# radio1.net
KiCad netlist of a schematic drawn in EAGLE
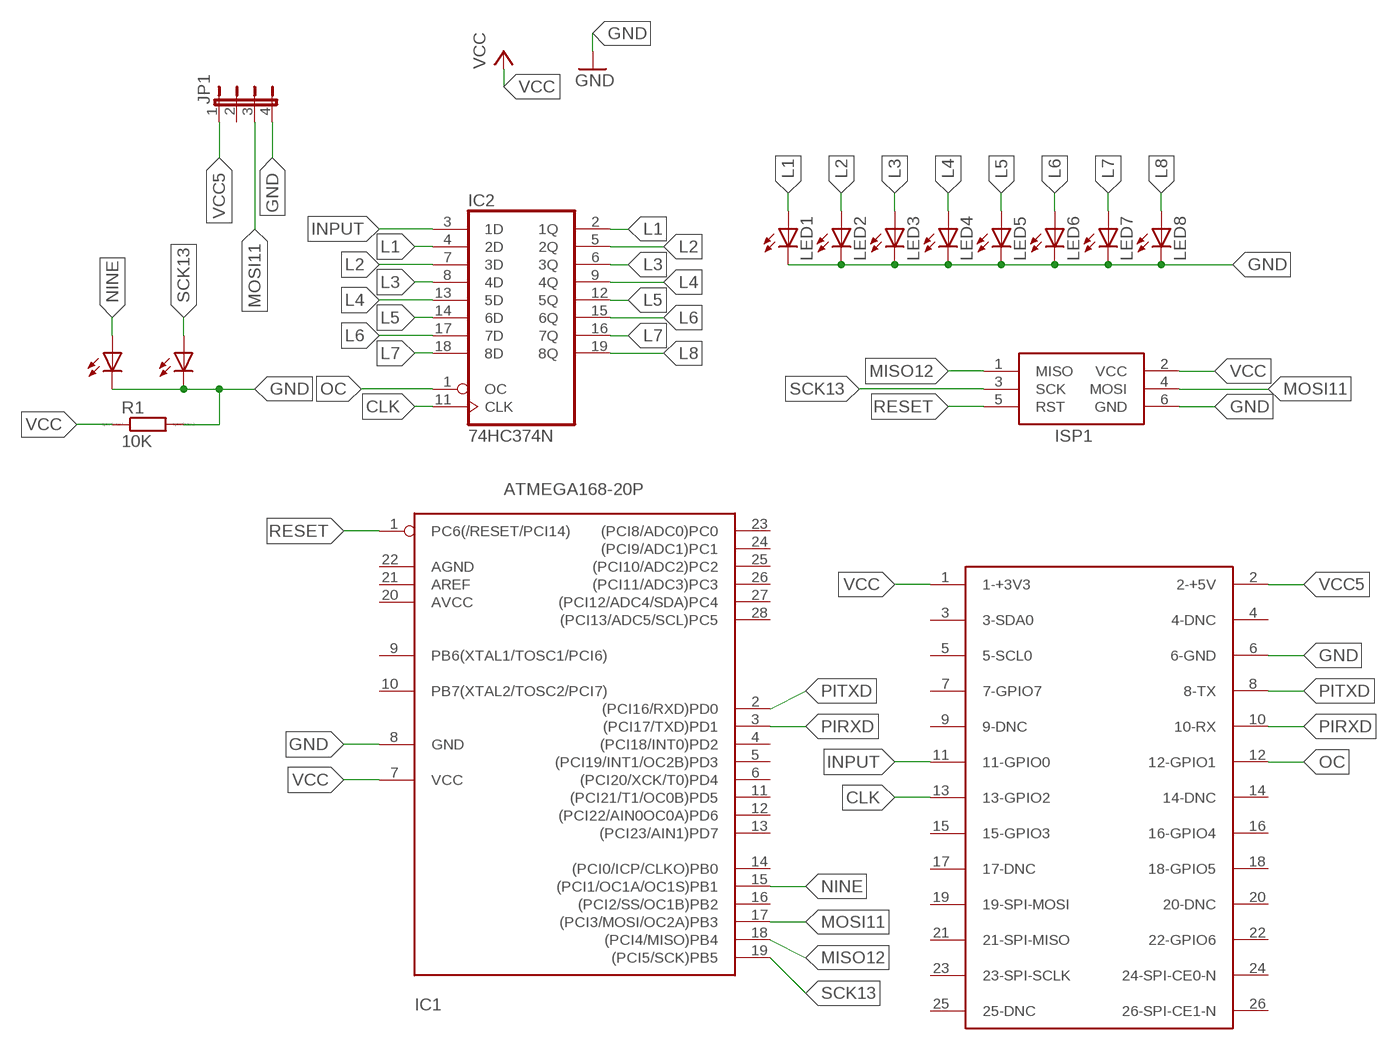
[diagram p0: schematic, sheet 1]

(export (version "E")
  (design (tool "Eeschema 10.0.6"))
  (components
    (comp (ref "IC1")
      (value "ATMEGA168-20P")
      (footprint "eagle-import:DIL28-3")
      (libsource (lib "eagle-import") (part "ATMEGA168P-20"))
    )
    (comp (ref "IC2")
      (value "74HC374N")
      (footprint "eagle-import:DIL20")
      (libsource (lib "eagle-import") (part "74374NHC"))
    )
    (comp (ref "ISP1")
      (value "AVRISP-6")
      (footprint "eagle-import:AVRISP")
      (libsource (lib "eagle-import") (part "AVRISP-6"))
    )
    (comp (ref "JP1")
      (value "JP4E")
      (footprint "eagle-import:JP4")
      (libsource (lib "eagle-import") (part "JP4E"))
    )
    (comp (ref "LED1")
      (value "LED3MM")
      (footprint "eagle-import:LED3MM")
      (libsource (lib "eagle-import") (part "LED3MM"))
    )
    (comp (ref "LED2")
      (value "LED3MM")
      (footprint "eagle-import:LED3MM")
      (libsource (lib "eagle-import") (part "LED3MM"))
    )
    (comp (ref "LED3")
      (value "LED3MM")
      (footprint "eagle-import:LED3MM")
      (libsource (lib "eagle-import") (part "LED3MM"))
    )
    (comp (ref "LED4")
      (value "LED3MM")
      (footprint "eagle-import:LED3MM")
      (libsource (lib "eagle-import") (part "LED3MM"))
    )
    (comp (ref "LED5")
      (value "LED3MM")
      (footprint "eagle-import:LED3MM")
      (libsource (lib "eagle-import") (part "LED3MM"))
    )
    (comp (ref "LED6")
      (value "LED3MM")
      (footprint "eagle-import:LED3MM")
      (libsource (lib "eagle-import") (part "LED3MM"))
    )
    (comp (ref "LED7")
      (value "LED3MM")
      (footprint "eagle-import:LED3MM")
      (libsource (lib "eagle-import") (part "LED3MM"))
    )
    (comp (ref "LED8")
      (value "LED3MM")
      (footprint "eagle-import:LED3MM")
      (libsource (lib "eagle-import") (part "LED3MM"))
    )
    (comp (ref "LED9")
      (value "LED3MM")
      (footprint "eagle-import:LED3MM")
      (libsource (lib "eagle-import") (part "LED3MM"))
    )
    (comp (ref "LED10")
      (value "LED3MM")
      (footprint "eagle-import:LED3MM")
      (libsource (lib "eagle-import") (part "LED3MM"))
    )
    (comp (ref "R1")
      (value "10K")
      (footprint "eagle-import:0204_7")
      (libsource (lib "eagle-import") (part "R-EU_0204_7"))
    )
    (comp (ref "U$1")
      (value "RASPBERRY-PI")
      (footprint "eagle-import:RASPBERRY-PI")
      (libsource (lib "eagle-import") (part "RASPBERRY-PI"))
    )
  )
  (nets
    (net (code "1") (name "CLK") (class "Default")
      (node (ref "IC2") (pin "11") (pinfunction "CLK_11") (pintype "input"))
      (node (ref "U$1") (pin "13") (pinfunction "13-GPIO2_13") (pintype "bidirectional"))
    )
    (net (code "2") (name "GND") (class "Default")
      (node (ref "IC1") (pin "8") (pinfunction "GND_8") (pintype "bidirectional"))
      (node (ref "ISP1") (pin "6") (pinfunction "GND_6") (pintype "power_in"))
      (node (ref "JP1") (pin "4") (pinfunction "4_4") (pintype "passive"))
      (node (ref "LED1") (pin "K") (pinfunction "C_K") (pintype "passive"))
      (node (ref "LED10") (pin "K") (pinfunction "C_K") (pintype "passive"))
      (node (ref "LED2") (pin "K") (pinfunction "C_K") (pintype "passive"))
      (node (ref "LED3") (pin "K") (pinfunction "C_K") (pintype "passive"))
      (node (ref "LED4") (pin "K") (pinfunction "C_K") (pintype "passive"))
      (node (ref "LED5") (pin "K") (pinfunction "C_K") (pintype "passive"))
      (node (ref "LED6") (pin "K") (pinfunction "C_K") (pintype "passive"))
      (node (ref "LED7") (pin "K") (pinfunction "C_K") (pintype "passive"))
      (node (ref "LED8") (pin "K") (pinfunction "C_K") (pintype "passive"))
      (node (ref "LED9") (pin "K") (pinfunction "C_K") (pintype "passive"))
      (node (ref "R1") (pin "2") (pinfunction "2_2") (pintype "passive"))
      (node (ref "U$1") (pin "6") (pinfunction "6-GND_6") (pintype "bidirectional"))
    )
    (net (code "3") (name "INPUT") (class "Default")
      (node (ref "IC2") (pin "3") (pinfunction "1D_3") (pintype "input"))
      (node (ref "U$1") (pin "11") (pinfunction "11-GPIO0_11") (pintype "bidirectional"))
    )
    (net (code "4") (name "L1") (class "Default")
      (node (ref "IC2") (pin "2") (pinfunction "1Q_2") (pintype "tri_state"))
      (node (ref "IC2") (pin "4") (pinfunction "2D_4") (pintype "input"))
      (node (ref "LED1") (pin "A") (pinfunction "A_A") (pintype "passive"))
    )
    (net (code "5") (name "L2") (class "Default")
      (node (ref "IC2") (pin "5") (pinfunction "2Q_5") (pintype "tri_state"))
      (node (ref "IC2") (pin "7") (pinfunction "3D_7") (pintype "input"))
      (node (ref "LED2") (pin "A") (pinfunction "A_A") (pintype "passive"))
    )
    (net (code "6") (name "L3") (class "Default")
      (node (ref "IC2") (pin "6") (pinfunction "3Q_6") (pintype "tri_state"))
      (node (ref "IC2") (pin "8") (pinfunction "4D_8") (pintype "input"))
      (node (ref "LED3") (pin "A") (pinfunction "A_A") (pintype "passive"))
    )
    (net (code "7") (name "L4") (class "Default")
      (node (ref "IC2") (pin "13") (pinfunction "5D_13") (pintype "input"))
      (node (ref "IC2") (pin "9") (pinfunction "4Q_9") (pintype "tri_state"))
      (node (ref "LED4") (pin "A") (pinfunction "A_A") (pintype "passive"))
    )
    (net (code "8") (name "L5") (class "Default")
      (node (ref "IC2") (pin "12") (pinfunction "5Q_12") (pintype "tri_state"))
      (node (ref "IC2") (pin "14") (pinfunction "6D_14") (pintype "input"))
      (node (ref "LED5") (pin "A") (pinfunction "A_A") (pintype "passive"))
    )
    (net (code "9") (name "L6") (class "Default")
      (node (ref "IC2") (pin "15") (pinfunction "6Q_15") (pintype "tri_state"))
      (node (ref "IC2") (pin "17") (pinfunction "7D_17") (pintype "input"))
      (node (ref "LED6") (pin "A") (pinfunction "A_A") (pintype "passive"))
    )
    (net (code "10") (name "L7") (class "Default")
      (node (ref "IC2") (pin "16") (pinfunction "7Q_16") (pintype "tri_state"))
      (node (ref "IC2") (pin "18") (pinfunction "8D_18") (pintype "input"))
      (node (ref "LED7") (pin "A") (pinfunction "A_A") (pintype "passive"))
    )
    (net (code "11") (name "L8") (class "Default")
      (node (ref "IC2") (pin "19") (pinfunction "8Q_19") (pintype "tri_state"))
      (node (ref "LED8") (pin "A") (pinfunction "A_A") (pintype "passive"))
    )
    (net (code "12") (name "MISO12") (class "Default")
      (node (ref "IC1") (pin "18") (pinfunction "(PCI4/MISO)PB4_18") (pintype "bidirectional"))
      (node (ref "ISP1") (pin "1") (pinfunction "MISO_1") (pintype "input"))
    )
    (net (code "13") (name "MOSI11") (class "Default")
      (node (ref "IC1") (pin "17") (pinfunction "(PCI3/MOSI/OC2A)PB3_17") (pintype "bidirectional"))
      (node (ref "ISP1") (pin "4") (pinfunction "MOSI_4") (pintype "output"))
      (node (ref "JP1") (pin "3") (pinfunction "3_3") (pintype "passive"))
    )
    (net (code "14") (name "NINE") (class "Default")
      (node (ref "IC1") (pin "15") (pinfunction "(PCI1/OC1A/OC1S)PB1_15") (pintype "bidirectional"))
      (node (ref "LED9") (pin "A") (pinfunction "A_A") (pintype "passive"))
    )
    (net (code "15") (name "OC") (class "Default")
      (node (ref "IC2") (pin "1") (pinfunction "OC_1") (pintype "input"))
      (node (ref "U$1") (pin "12") (pinfunction "12-GPIO1_12") (pintype "bidirectional"))
    )
    (net (code "16") (name "PIRXD") (class "Default")
      (node (ref "IC1") (pin "3") (pinfunction "(PCI17/TXD)PD1_3") (pintype "bidirectional"))
      (node (ref "U$1") (pin "10") (pinfunction "10-RX_10") (pintype "bidirectional"))
    )
    (net (code "17") (name "PITXD") (class "Default")
      (node (ref "IC1") (pin "2") (pinfunction "(PCI16/RXD)PD0_2") (pintype "bidirectional"))
      (node (ref "U$1") (pin "8") (pinfunction "8-TX_8") (pintype "bidirectional"))
    )
    (net (code "18") (name "RESET") (class "Default")
      (node (ref "IC1") (pin "1") (pinfunction "PC6(/RESET/PCI14)_1") (pintype "bidirectional"))
      (node (ref "ISP1") (pin "5") (pinfunction "RST_5") (pintype "output"))
    )
    (net (code "19") (name "SCK13") (class "Default")
      (node (ref "IC1") (pin "19") (pinfunction "(PCI5/SCK)PB5_19") (pintype "bidirectional"))
      (node (ref "ISP1") (pin "3") (pinfunction "SCK_3") (pintype "output"))
      (node (ref "LED10") (pin "A") (pinfunction "A_A") (pintype "passive"))
    )
    (net (code "20") (name "VCC") (class "Default")
      (node (ref "IC1") (pin "7") (pinfunction "VCC_7") (pintype "bidirectional"))
      (node (ref "ISP1") (pin "2") (pinfunction "VCC_2") (pintype "power_in"))
      (node (ref "R1") (pin "1") (pinfunction "1_1") (pintype "passive"))
      (node (ref "U$1") (pin "1") (pinfunction "1-+3V3_1") (pintype "bidirectional"))
    )
    (net (code "21") (name "VCC5") (class "Default")
      (node (ref "JP1") (pin "1") (pinfunction "1_1") (pintype "passive"))
      (node (ref "U$1") (pin "2") (pinfunction "2-+5V_2") (pintype "bidirectional"))
    )
    (net (code "22") (name "unconnected-(IC1-(PCI0{slash}ICP{slash}CLKO)PB0-Pad14)") (class "Default")
      (node (ref "IC1") (pin "14") (pinfunction "(PCI0/ICP/CLKO)PB0_14") (pintype "bidirectional"))
    )
    (net (code "23") (name "unconnected-(IC1-(PCI2{slash}SS{slash}OC1B)PB2-Pad16)") (class "Default")
      (node (ref "IC1") (pin "16") (pinfunction "(PCI2/SS/OC1B)PB2_16") (pintype "bidirectional"))
    )
    (net (code "24") (name "unconnected-(IC1-(PCI8{slash}ADC0)PC0-Pad23)") (class "Default")
      (node (ref "IC1") (pin "23") (pinfunction "(PCI8/ADC0)PC0_23") (pintype "bidirectional"))
    )
    (net (code "25") (name "unconnected-(IC1-(PCI9{slash}ADC1)PC1-Pad24)") (class "Default")
      (node (ref "IC1") (pin "24") (pinfunction "(PCI9/ADC1)PC1_24") (pintype "bidirectional"))
    )
    (net (code "26") (name "unconnected-(IC1-(PCI10{slash}ADC2)PC2-Pad25)") (class "Default")
      (node (ref "IC1") (pin "25") (pinfunction "(PCI10/ADC2)PC2_25") (pintype "bidirectional"))
    )
    (net (code "27") (name "unconnected-(IC1-(PCI11{slash}ADC3)PC3-Pad26)") (class "Default")
      (node (ref "IC1") (pin "26") (pinfunction "(PCI11/ADC3)PC3_26") (pintype "bidirectional"))
    )
    (net (code "28") (name "unconnected-(IC1-(PCI12{slash}ADC4{slash}SDA)PC4-Pad27)") (class "Default")
      (node (ref "IC1") (pin "27") (pinfunction "(PCI12/ADC4/SDA)PC4_27") (pintype "bidirectional"))
    )
    (net (code "29") (name "unconnected-(IC1-(PCI13{slash}ADC5{slash}SCL)PC5-Pad28)") (class "Default")
      (node (ref "IC1") (pin "28") (pinfunction "(PCI13/ADC5/SCL)PC5_28") (pintype "bidirectional"))
    )
    (net (code "30") (name "unconnected-(IC1-(PCI18{slash}INT0)PD2-Pad4)") (class "Default")
      (node (ref "IC1") (pin "4") (pinfunction "(PCI18/INT0)PD2_4") (pintype "bidirectional"))
    )
    (net (code "31") (name "unconnected-(IC1-(PCI19{slash}INT1{slash}OC2B)PD3-Pad5)") (class "Default")
      (node (ref "IC1") (pin "5") (pinfunction "(PCI19/INT1/OC2B)PD3_5") (pintype "bidirectional"))
    )
    (net (code "32") (name "unconnected-(IC1-(PCI20{slash}XCK{slash}T0)PD4-Pad6)") (class "Default")
      (node (ref "IC1") (pin "6") (pinfunction "(PCI20/XCK/T0)PD4_6") (pintype "bidirectional"))
    )
    (net (code "33") (name "unconnected-(IC1-(PCI21{slash}T1{slash}OC0B)PD5-Pad11)") (class "Default")
      (node (ref "IC1") (pin "11") (pinfunction "(PCI21/T1/OC0B)PD5_11") (pintype "bidirectional"))
    )
    (net (code "34") (name "unconnected-(IC1-(PCI22{slash}AIN0OC0A)PD6-Pad12)") (class "Default")
      (node (ref "IC1") (pin "12") (pinfunction "(PCI22/AIN0OC0A)PD6_12") (pintype "bidirectional"))
    )
    (net (code "35") (name "unconnected-(IC1-(PCI23{slash}AIN1)PD7-Pad13)") (class "Default")
      (node (ref "IC1") (pin "13") (pinfunction "(PCI23/AIN1)PD7_13") (pintype "bidirectional"))
    )
    (net (code "36") (name "unconnected-(IC1-AGND-Pad22)") (class "Default")
      (node (ref "IC1") (pin "22") (pinfunction "AGND_22") (pintype "bidirectional"))
    )
    (net (code "37") (name "unconnected-(IC1-AREF-Pad21)") (class "Default")
      (node (ref "IC1") (pin "21") (pinfunction "AREF_21") (pintype "bidirectional"))
    )
    (net (code "38") (name "unconnected-(IC1-AVCC-Pad20)") (class "Default")
      (node (ref "IC1") (pin "20") (pinfunction "AVCC_20") (pintype "bidirectional"))
    )
    (net (code "39") (name "unconnected-(IC1-PB6(XTAL1{slash}TOSC1{slash}PCI6)-Pad9)") (class "Default")
      (node (ref "IC1") (pin "9") (pinfunction "PB6(XTAL1/TOSC1/PCI6)_9") (pintype "bidirectional"))
    )
    (net (code "40") (name "unconnected-(IC1-PB7(XTAL2{slash}TOSC2{slash}PCI7)-Pad10)") (class "Default")
      (node (ref "IC1") (pin "10") (pinfunction "PB7(XTAL2/TOSC2/PCI7)_10") (pintype "bidirectional"))
    )
    (net (code "41") (name "unconnected-(JP1-Pad2)") (class "Default")
      (node (ref "JP1") (pin "2") (pinfunction "2_2") (pintype "passive"))
    )
    (net (code "42") (name "unconnected-(U$1-3-SDA0-Pad3)") (class "Default")
      (node (ref "U$1") (pin "3") (pinfunction "3-SDA0_3") (pintype "bidirectional"))
    )
    (net (code "43") (name "unconnected-(U$1-4-DNC-Pad4)") (class "Default")
      (node (ref "U$1") (pin "4") (pinfunction "4-DNC_4") (pintype "bidirectional"))
    )
    (net (code "44") (name "unconnected-(U$1-5-SCL0-Pad5)") (class "Default")
      (node (ref "U$1") (pin "5") (pinfunction "5-SCL0_5") (pintype "bidirectional"))
    )
    (net (code "45") (name "unconnected-(U$1-7-GPIO7-Pad7)") (class "Default")
      (node (ref "U$1") (pin "7") (pinfunction "7-GPIO7_7") (pintype "bidirectional"))
    )
    (net (code "46") (name "unconnected-(U$1-9-DNC-Pad9)") (class "Default")
      (node (ref "U$1") (pin "9") (pinfunction "9-DNC_9") (pintype "bidirectional"))
    )
    (net (code "47") (name "unconnected-(U$1-14-DNC-Pad14)") (class "Default")
      (node (ref "U$1") (pin "14") (pinfunction "14-DNC_14") (pintype "bidirectional"))
    )
    (net (code "48") (name "unconnected-(U$1-15-GPIO3-Pad15)") (class "Default")
      (node (ref "U$1") (pin "15") (pinfunction "15-GPIO3_15") (pintype "bidirectional"))
    )
    (net (code "49") (name "unconnected-(U$1-16-GPIO4-Pad16)") (class "Default")
      (node (ref "U$1") (pin "16") (pinfunction "16-GPIO4_16") (pintype "bidirectional"))
    )
    (net (code "50") (name "unconnected-(U$1-17-DNC-Pad17)") (class "Default")
      (node (ref "U$1") (pin "17") (pinfunction "17-DNC_17") (pintype "bidirectional"))
    )
    (net (code "51") (name "unconnected-(U$1-18-GPIO5-Pad18)") (class "Default")
      (node (ref "U$1") (pin "18") (pinfunction "18-GPIO5_18") (pintype "bidirectional"))
    )
    (net (code "52") (name "unconnected-(U$1-19-SPI-MOSI-Pad19)") (class "Default")
      (node (ref "U$1") (pin "19") (pinfunction "19-SPI-MOSI_19") (pintype "bidirectional"))
    )
    (net (code "53") (name "unconnected-(U$1-20-DNC-Pad20)") (class "Default")
      (node (ref "U$1") (pin "20") (pinfunction "20-DNC_20") (pintype "bidirectional"))
    )
    (net (code "54") (name "unconnected-(U$1-21-SPI-MISO-Pad21)") (class "Default")
      (node (ref "U$1") (pin "21") (pinfunction "21-SPI-MISO_21") (pintype "bidirectional"))
    )
    (net (code "55") (name "unconnected-(U$1-22-GPIO6-Pad22)") (class "Default")
      (node (ref "U$1") (pin "22") (pinfunction "22-GPIO6_22") (pintype "bidirectional"))
    )
    (net (code "56") (name "unconnected-(U$1-23-SPI-SCLK-Pad23)") (class "Default")
      (node (ref "U$1") (pin "23") (pinfunction "23-SPI-SCLK_23") (pintype "bidirectional"))
    )
    (net (code "57") (name "unconnected-(U$1-24-SPI-CE0-N-Pad24)") (class "Default")
      (node (ref "U$1") (pin "24") (pinfunction "24-SPI-CE0-N_24") (pintype "bidirectional"))
    )
    (net (code "58") (name "unconnected-(U$1-25-DNC-Pad25)") (class "Default")
      (node (ref "U$1") (pin "25") (pinfunction "25-DNC_25") (pintype "bidirectional"))
    )
    (net (code "59") (name "unconnected-(U$1-26-SPI-CE1-N-Pad26)") (class "Default")
      (node (ref "U$1") (pin "26") (pinfunction "26-SPI-CE1-N_26") (pintype "bidirectional"))
    )
  )
)
